# centerbody_logic.net
KiCad netlist of a schematic drawn in EAGLE
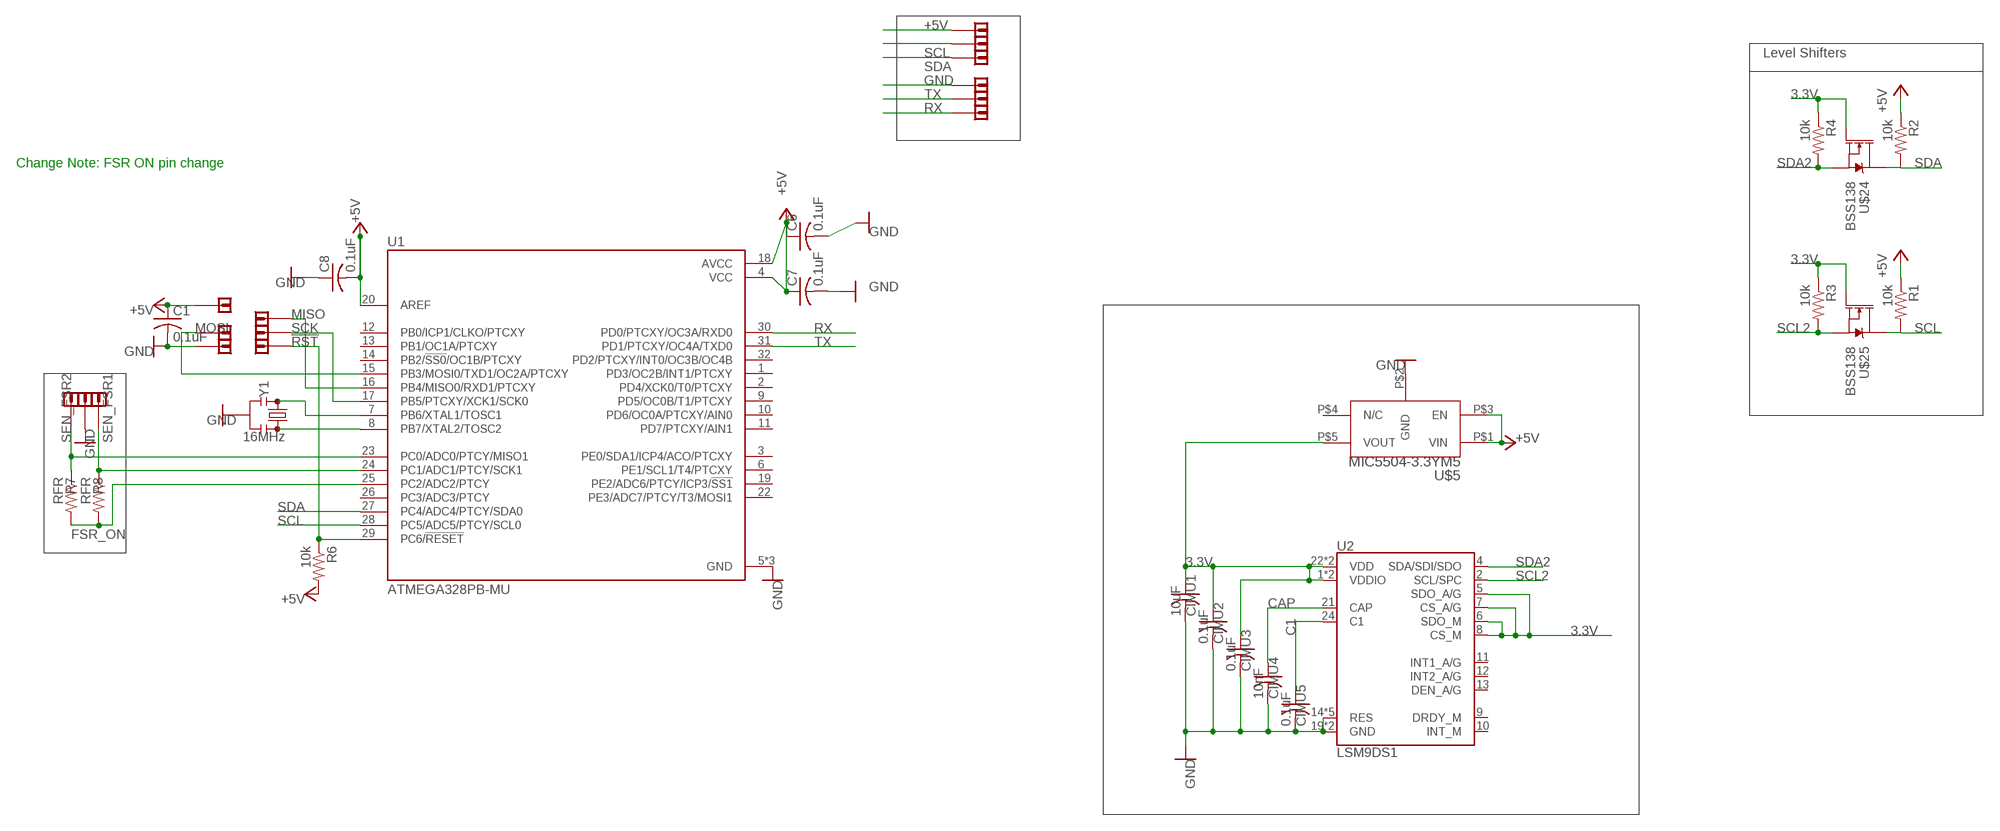
[diagram p0: schematic, sheet 1]

(export (version "E")
  (design (tool "Eeschema 10.0.6"))
  (components
    (comp (ref "C1")
      (value "0.1uF")
      (footprint "eagle-import:C0402")
      (fields (field (name "PARTNO") "885012105010"))
      (libsource (lib "eagle-import") (part "C-USC0402"))
    )
    (comp (ref "C6")
      (value "0.1uF")
      (footprint "eagle-import:C0402")
      (fields (field (name "PARTNO") "885012105010"))
      (libsource (lib "eagle-import") (part "C-USC0402"))
    )
    (comp (ref "C7")
      (value "0.1uF")
      (footprint "eagle-import:C0402")
      (fields (field (name "PARTNO") "885012105010"))
      (libsource (lib "eagle-import") (part "C-USC0402"))
    )
    (comp (ref "C8")
      (value "0.1uF")
      (footprint "eagle-import:C0402")
      (fields (field (name "PARTNO") "885012105010"))
      (libsource (lib "eagle-import") (part "C-USC0402"))
    )
    (comp (ref "CIMU1")
      (value "10uF")
      (footprint "eagle-import:C0402")
      (fields (field (name "PARTNO") "GRM155R60G106ME44D"))
      (libsource (lib "eagle-import") (part "C-USC0402"))
    )
    (comp (ref "CIMU2")
      (value "0.1uF")
      (footprint "eagle-import:C0402")
      (fields (field (name "PARTNO") "885012105010"))
      (libsource (lib "eagle-import") (part "C-USC0402"))
    )
    (comp (ref "CIMU3")
      (value "0.1uF")
      (footprint "eagle-import:C0402")
      (fields (field (name "PARTNO") "885012105010"))
      (libsource (lib "eagle-import") (part "C-USC0402"))
    )
    (comp (ref "CIMU4")
      (value "10nF")
      (footprint "eagle-import:C0402")
      (fields (field (name "PARTNO") "CL05B103KB5NNNC"))
      (libsource (lib "eagle-import") (part "C-USC0402"))
    )
    (comp (ref "CIMU5")
      (value "0.1uF")
      (footprint "eagle-import:C0402")
      (fields (field (name "PARTNO") "885012105010"))
      (libsource (lib "eagle-import") (part "C-USC0402"))
    )
    (comp (ref "R1")
      (value "10k")
      (footprint "eagle-import:R0402")
      (fields (field (name "PARTNO") "RR0510P-103-D"))
      (libsource (lib "eagle-import") (part "R-US_R0402"))
    )
    (comp (ref "R2")
      (value "10k")
      (footprint "eagle-import:R0402")
      (fields (field (name "PARTNO") "RR0510P-103-D"))
      (libsource (lib "eagle-import") (part "R-US_R0402"))
    )
    (comp (ref "R3")
      (value "10k")
      (footprint "eagle-import:R0402")
      (fields (field (name "PARTNO") "RR0510P-103-D"))
      (libsource (lib "eagle-import") (part "R-US_R0402"))
    )
    (comp (ref "R4")
      (value "10k")
      (footprint "eagle-import:R0402")
      (fields (field (name "PARTNO") "RR0510P-103-D"))
      (libsource (lib "eagle-import") (part "R-US_R0402"))
    )
    (comp (ref "R6")
      (value "10k")
      (footprint "eagle-import:R0402")
      (fields (field (name "PARTNO") "RR0510P-103-D"))
      (libsource (lib "eagle-import") (part "R-US_R0402"))
    )
    (comp (ref "R7")
      (value "RFR")
      (footprint "eagle-import:R0402")
      (fields (field (name "PARTNO") "CRGCQ0402F5K6"))
      (libsource (lib "eagle-import") (part "R-US_R0402"))
    )
    (comp (ref "R8")
      (value "RFR")
      (footprint "eagle-import:R0402")
      (fields (field (name "PARTNO") "CRGCQ0402F5K6"))
      (libsource (lib "eagle-import") (part "R-US_R0402"))
    )
    (comp (ref "U$1")
      (value "SIMPLE_VIA_CONNECTION")
      (footprint "eagle-import:SIMPLEVIA")
      (libsource (lib "eagle-import") (part "SIMPLE_VIA_CONNECTION"))
    )
    (comp (ref "U$3")
      (value "SIMPLE_VIA_CONNECTION")
      (footprint "eagle-import:SIMPLEVIA")
      (libsource (lib "eagle-import") (part "SIMPLE_VIA_CONNECTION"))
    )
    (comp (ref "U$4")
      (value "SIMPLE_VIA_CONNECTION")
      (footprint "eagle-import:SIMPLEVIA")
      (libsource (lib "eagle-import") (part "SIMPLE_VIA_CONNECTION"))
    )
    (comp (ref "U$5")
      (value "MIC5504-3.3YM5")
      (footprint "eagle-import:SOT23")
      (fields (field (name "PARTNO") "MIC5504-3.3YM5-TR"))
      (libsource (lib "eagle-import") (part "MIC5504-3.3YM5"))
    )
    (comp (ref "U$6")
      (value "SIMPLE_VIA_CONNECTION")
      (footprint "eagle-import:SIMPLEVIA")
      (libsource (lib "eagle-import") (part "SIMPLE_VIA_CONNECTION"))
    )
    (comp (ref "U$7")
      (value "SIMPLE_VIA_CONNECTION")
      (footprint "eagle-import:SIMPLEVIA")
      (libsource (lib "eagle-import") (part "SIMPLE_VIA_CONNECTION"))
    )
    (comp (ref "U$8")
      (value "SIMPLE_VIA_CONNECTION")
      (footprint "eagle-import:SIMPLEVIA")
      (libsource (lib "eagle-import") (part "SIMPLE_VIA_CONNECTION"))
    )
    (comp (ref "U$9")
      (value "SIMPLE_VIA_CONNECTION")
      (footprint "eagle-import:SIMPLEVIA")
      (libsource (lib "eagle-import") (part "SIMPLE_VIA_CONNECTION"))
    )
    (comp (ref "U$10")
      (value "SIMPLE_VIA_CONNECTION")
      (footprint "eagle-import:SIMPLEVIA")
      (libsource (lib "eagle-import") (part "SIMPLE_VIA_CONNECTION"))
    )
    (comp (ref "U$11")
      (value "SIMPLE_VIA_CONNECTION")
      (footprint "eagle-import:SIMPLEVIA")
      (libsource (lib "eagle-import") (part "SIMPLE_VIA_CONNECTION"))
    )
    (comp (ref "U$12")
      (value "SIMPLE_VIA_CONNECTION")
      (footprint "eagle-import:SIMPLEVIA")
      (libsource (lib "eagle-import") (part "SIMPLE_VIA_CONNECTION"))
    )
    (comp (ref "U$13")
      (value "SIMPLE_VIA_CONNECTION")
      (footprint "eagle-import:SIMPLEVIA")
      (libsource (lib "eagle-import") (part "SIMPLE_VIA_CONNECTION"))
    )
    (comp (ref "U$14")
      (value "SIMPLE_VIA_CONNECTION")
      (footprint "eagle-import:SIMPLEVIA")
      (libsource (lib "eagle-import") (part "SIMPLE_VIA_CONNECTION"))
    )
    (comp (ref "U$15")
      (value "SIMPLE_VIA_CONNECTION")
      (footprint "eagle-import:SIMPLEVIA")
      (libsource (lib "eagle-import") (part "SIMPLE_VIA_CONNECTION"))
    )
    (comp (ref "U$24")
      (value "BSS138")
      (footprint "eagle-import:SOT-23")
      (libsource (lib "eagle-import") (part "BSS138"))
    )
    (comp (ref "U$25")
      (value "BSS138")
      (footprint "eagle-import:SOT-23")
      (libsource (lib "eagle-import") (part "BSS138"))
    )
    (comp (ref "U$26")
      (value "SIMPLE_VIA_CONNECTION")
      (footprint "eagle-import:SIMPLEVIA")
      (libsource (lib "eagle-import") (part "SIMPLE_VIA_CONNECTION"))
    )
    (comp (ref "U$27")
      (value "SIMPLE_VIA_CONNECTION")
      (footprint "eagle-import:SIMPLEVIA")
      (libsource (lib "eagle-import") (part "SIMPLE_VIA_CONNECTION"))
    )
    (comp (ref "U1")
      (value "ATMEGA328PB-MU")
      (footprint "eagle-import:QFN50P500X500X90-33N")
      (fields
        (field (name "DIGI-KEY_PART_NUMBER") "ATMEGA328PB-MU-ND")
        (field (name "MF") "Microchip")
        (field (name "PARTNO") "ATMEGA328PB-MUR")
      )
      (libsource (lib "eagle-import") (part "ATMEGA328PB-MU"))
    )
    (comp (ref "U2")
      (value "LSM9DS1")
      (footprint "eagle-import:LGA24-8X4")
      (fields (field (name "PARTNO") "LSM9DS1TR"))
      (libsource (lib "eagle-import") (part "LSM9DS1"))
    )
    (comp (ref "Y1")
      (value "16MHz")
      (footprint "eagle-import:RESONATOR-SMD-3.2X1.3")
      (fields (field (name "PARTNO") "CSTNE16M0V530000R0"))
      (libsource (lib "eagle-import") (part "RESONATOR-16MHZSMD_3.2X1.3"))
    )
  )
  (nets
    (net (code "1") (name "+5V") (class "Default")
      (node (ref "C1") (pin "1") (pinfunction "1_1") (pintype "passive"))
      (node (ref "C6") (pin "1") (pinfunction "1_1") (pintype "passive"))
      (node (ref "C7") (pin "1") (pinfunction "1_1") (pintype "passive"))
      (node (ref "C8") (pin "2") (pinfunction "2_2") (pintype "passive"))
      (node (ref "R1") (pin "1") (pinfunction "1_1") (pintype "passive"))
      (node (ref "R2") (pin "1") (pinfunction "1_1") (pintype "passive"))
      (node (ref "R6") (pin "2") (pinfunction "2_2") (pintype "passive"))
      (node (ref "U$10") (pin "P$1") (pinfunction "1_P$1") (pintype "passive"))
      (node (ref "U$5") (pin "P$1") (pinfunction "VIN_P$1") (pintype "bidirectional"))
      (node (ref "U$5") (pin "P$3") (pinfunction "EN_P$3") (pintype "bidirectional"))
      (node (ref "U$7") (pin "P$1") (pinfunction "1_P$1") (pintype "passive"))
      (node (ref "U1") (pin "18") (pinfunction "AVCC_18") (pintype "power_in"))
      (node (ref "U1") (pin "20") (pinfunction "AREF_20") (pintype "input"))
      (node (ref "U1") (pin "4") (pinfunction "VCC_4") (pintype "power_in"))
    )
    (net (code "2") (name "/3.3V") (class "Default")
      (node (ref "CIMU1") (pin "1") (pinfunction "1_1") (pintype "passive"))
      (node (ref "CIMU2") (pin "1") (pinfunction "1_1") (pintype "passive"))
      (node (ref "CIMU3") (pin "1") (pinfunction "1_1") (pintype "passive"))
      (node (ref "R3") (pin "1") (pinfunction "1_1") (pintype "passive"))
      (node (ref "R4") (pin "1") (pinfunction "1_1") (pintype "passive"))
      (node (ref "U$24") (pin "P$1") (pinfunction "G_P$1") (pintype "bidirectional"))
      (node (ref "U$25") (pin "P$1") (pinfunction "G_P$1") (pintype "bidirectional"))
      (node (ref "U$5") (pin "P$5") (pinfunction "VOUT_P$5") (pintype "bidirectional"))
      (node (ref "U2") (pin "1") (pinfunction "VDDIO_1") (pintype "bidirectional"))
      (node (ref "U2") (pin "22") (pinfunction "VDD_22") (pintype "bidirectional"))
      (node (ref "U2") (pin "23") (pinfunction "VDD_23") (pintype "bidirectional"))
      (node (ref "U2") (pin "3") (pinfunction "VDDIO_3") (pintype "bidirectional"))
      (node (ref "U2") (pin "5") (pinfunction "SDO_A/G_5") (pintype "bidirectional"))
      (node (ref "U2") (pin "6") (pinfunction "SDO_M_6") (pintype "bidirectional"))
      (node (ref "U2") (pin "7") (pinfunction "CS_A/G_7") (pintype "bidirectional"))
      (node (ref "U2") (pin "8") (pinfunction "CS_M_8") (pintype "bidirectional"))
    )
    (net (code "3") (name "/C1") (class "Default")
      (node (ref "CIMU5") (pin "1") (pinfunction "1_1") (pintype "passive"))
      (node (ref "U2") (pin "24") (pinfunction "C1_24") (pintype "bidirectional"))
    )
    (net (code "4") (name "/CAP") (class "Default")
      (node (ref "CIMU4") (pin "1") (pinfunction "1_1") (pintype "passive"))
      (node (ref "U2") (pin "21") (pinfunction "CAP_21") (pintype "bidirectional"))
    )
    (net (code "5") (name "/FSR_ON") (class "Default")
      (node (ref "R7") (pin "2") (pinfunction "2_2") (pintype "passive"))
      (node (ref "R8") (pin "2") (pinfunction "2_2") (pintype "passive"))
      (node (ref "U1") (pin "25") (pinfunction "PC2/ADC2/PTCY_25") (pintype "bidirectional"))
    )
    (net (code "6") (name "/MISO") (class "Default")
      (node (ref "U$15") (pin "P$1") (pinfunction "1_P$1") (pintype "passive"))
      (node (ref "U1") (pin "16") (pinfunction "PB4/MISO0/RXD1/PTCXY_16") (pintype "bidirectional"))
    )
    (net (code "7") (name "/MOSI") (class "Default")
      (node (ref "U$11") (pin "P$1") (pinfunction "1_P$1") (pintype "passive"))
      (node (ref "U1") (pin "15") (pinfunction "PB3/MOSI0/TXD1/OC2A/PTCXY_15") (pintype "bidirectional"))
    )
    (net (code "8") (name "/RX") (class "Default")
      (node (ref "U$27") (pin "P$1") (pinfunction "1_P$1") (pintype "passive"))
      (node (ref "U1") (pin "30") (pinfunction "PD0/PTCXY/OC3A/RXD0_30") (pintype "bidirectional"))
    )
    (net (code "9") (name "/SCK") (class "Default")
      (node (ref "U$14") (pin "P$1") (pinfunction "1_P$1") (pintype "passive"))
      (node (ref "U1") (pin "17") (pinfunction "PB5/PTCXY/XCK1/SCK0_17") (pintype "bidirectional"))
    )
    (net (code "10") (name "/SCL") (class "Default")
      (node (ref "R1") (pin "2") (pinfunction "2_2") (pintype "passive"))
      (node (ref "U$25") (pin "P$3") (pinfunction "D_P$3") (pintype "bidirectional"))
      (node (ref "U$9") (pin "P$1") (pinfunction "1_P$1") (pintype "passive"))
      (node (ref "U1") (pin "28") (pinfunction "PC5/ADC5/PTCY/SCL0_28") (pintype "bidirectional"))
    )
    (net (code "11") (name "/SCL2") (class "Default")
      (node (ref "R3") (pin "2") (pinfunction "2_2") (pintype "passive"))
      (node (ref "U$25") (pin "P$2") (pinfunction "S_P$2") (pintype "bidirectional"))
      (node (ref "U2") (pin "2") (pinfunction "SCL/SPC_2") (pintype "bidirectional"))
    )
    (net (code "12") (name "/SDA") (class "Default")
      (node (ref "R2") (pin "2") (pinfunction "2_2") (pintype "passive"))
      (node (ref "U$24") (pin "P$3") (pinfunction "D_P$3") (pintype "bidirectional"))
      (node (ref "U$4") (pin "P$1") (pinfunction "1_P$1") (pintype "passive"))
      (node (ref "U1") (pin "27") (pinfunction "PC4/ADC4/PTCY/SDA0_27") (pintype "bidirectional"))
    )
    (net (code "13") (name "/SDA2") (class "Default")
      (node (ref "R4") (pin "2") (pinfunction "2_2") (pintype "passive"))
      (node (ref "U$24") (pin "P$2") (pinfunction "S_P$2") (pintype "bidirectional"))
      (node (ref "U2") (pin "4") (pinfunction "SDA/SDI/SDO_4") (pintype "bidirectional"))
    )
    (net (code "14") (name "/SEN_FSR1") (class "Default")
      (node (ref "R8") (pin "1") (pinfunction "1_1") (pintype "passive"))
      (node (ref "U$8") (pin "P$1") (pinfunction "1_P$1") (pintype "passive"))
      (node (ref "U1") (pin "24") (pinfunction "PC1/ADC1/PTCY/SCK1_24") (pintype "bidirectional"))
    )
    (net (code "15") (name "/SEN_FSR2") (class "Default")
      (node (ref "R7") (pin "1") (pinfunction "1_1") (pintype "passive"))
      (node (ref "U$1") (pin "P$1") (pinfunction "1_P$1") (pintype "passive"))
      (node (ref "U1") (pin "23") (pinfunction "PC0/ADC0/PTCY/MISO1_23") (pintype "bidirectional"))
    )
    (net (code "16") (name "/TX") (class "Default")
      (node (ref "U$26") (pin "P$1") (pinfunction "1_P$1") (pintype "passive"))
      (node (ref "U1") (pin "31") (pinfunction "PD1/PTCXY/OC4A/TXD0_31") (pintype "bidirectional"))
    )
    (net (code "17") (name "/~{RST}") (class "Default")
      (node (ref "R6") (pin "1") (pinfunction "1_1") (pintype "passive"))
      (node (ref "U$13") (pin "P$1") (pinfunction "1_P$1") (pintype "passive"))
      (node (ref "U1") (pin "29") (pinfunction "PC6/~{RESET}_29") (pintype "bidirectional"))
    )
    (net (code "18") (name "GND") (class "Default")
      (node (ref "C1") (pin "2") (pinfunction "2_2") (pintype "passive"))
      (node (ref "C6") (pin "2") (pinfunction "2_2") (pintype "passive"))
      (node (ref "C7") (pin "2") (pinfunction "2_2") (pintype "passive"))
      (node (ref "C8") (pin "1") (pinfunction "1_1") (pintype "passive"))
      (node (ref "CIMU1") (pin "2") (pinfunction "2_2") (pintype "passive"))
      (node (ref "CIMU2") (pin "2") (pinfunction "2_2") (pintype "passive"))
      (node (ref "CIMU3") (pin "2") (pinfunction "2_2") (pintype "passive"))
      (node (ref "CIMU4") (pin "2") (pinfunction "2_2") (pintype "passive"))
      (node (ref "CIMU5") (pin "2") (pinfunction "2_2") (pintype "passive"))
      (node (ref "U$12") (pin "P$1") (pinfunction "1_P$1") (pintype "passive"))
      (node (ref "U$3") (pin "P$1") (pinfunction "1_P$1") (pintype "passive"))
      (node (ref "U$5") (pin "P$2") (pinfunction "GND_P$2") (pintype "bidirectional"))
      (node (ref "U$6") (pin "P$1") (pinfunction "1_P$1") (pintype "passive"))
      (node (ref "U1") (pin "21") (pinfunction "GND_21") (pintype "power_in"))
      (node (ref "U1") (pin "33") (pinfunction "GND_33") (pintype "power_in"))
      (node (ref "U1") (pin "5") (pinfunction "GND_5") (pintype "power_in"))
      (node (ref "U2") (pin "14") (pinfunction "RES_14") (pintype "bidirectional"))
      (node (ref "U2") (pin "15") (pinfunction "RES_15") (pintype "bidirectional"))
      (node (ref "U2") (pin "16") (pinfunction "RES_16") (pintype "bidirectional"))
      (node (ref "U2") (pin "17") (pinfunction "RES_17") (pintype "bidirectional"))
      (node (ref "U2") (pin "18") (pinfunction "RES_18") (pintype "bidirectional"))
      (node (ref "U2") (pin "19") (pinfunction "GND_19") (pintype "bidirectional"))
      (node (ref "U2") (pin "20") (pinfunction "GND_20") (pintype "bidirectional"))
      (node (ref "Y1") (pin "2") (pinfunction "2_2") (pintype "passive"))
    )
    (net (code "19") (name "Net-(U1-PB6{slash}XTAL1{slash}TOSC1)") (class "Default")
      (node (ref "U1") (pin "7") (pinfunction "PB6/XTAL1/TOSC1_7") (pintype "bidirectional"))
      (node (ref "Y1") (pin "1") (pinfunction "1_1") (pintype "passive"))
    )
    (net (code "20") (name "Net-(U1-PB7{slash}XTAL2{slash}TOSC2)") (class "Default")
      (node (ref "U1") (pin "8") (pinfunction "PB7/XTAL2/TOSC2_8") (pintype "bidirectional"))
      (node (ref "Y1") (pin "3") (pinfunction "3_3") (pintype "passive"))
    )
    (net (code "21") (name "unconnected-(U$5-N{slash}C-PadP$4)") (class "Default")
      (node (ref "U$5") (pin "P$4") (pinfunction "N/C_P$4") (pintype "bidirectional"))
    )
    (net (code "22") (name "unconnected-(U1-PB0{slash}ICP1{slash}CLKO{slash}PTCXY-Pad12)") (class "Default")
      (node (ref "U1") (pin "12") (pinfunction "PB0/ICP1/CLKO/PTCXY_12") (pintype "bidirectional"))
    )
    (net (code "23") (name "unconnected-(U1-PB1{slash}OC1A{slash}PTCXY-Pad13)") (class "Default")
      (node (ref "U1") (pin "13") (pinfunction "PB1/OC1A/PTCXY_13") (pintype "bidirectional"))
    )
    (net (code "24") (name "unconnected-(U1-PB2{slash}~{SS0}{slash}OC1B{slash}PTCXY-Pad14)") (class "Default")
      (node (ref "U1") (pin "14") (pinfunction "PB2/~{SS0}/OC1B/PTCXY_14") (pintype "bidirectional"))
    )
    (net (code "25") (name "unconnected-(U1-PC3{slash}ADC3{slash}PTCY-Pad26)") (class "Default")
      (node (ref "U1") (pin "26") (pinfunction "PC3/ADC3/PTCY_26") (pintype "bidirectional"))
    )
    (net (code "26") (name "unconnected-(U1-PD2{slash}PTCXY{slash}INT0{slash}OC3B{slash}OC4B-Pad32)") (class "Default")
      (node (ref "U1") (pin "32") (pinfunction "PD2/PTCXY/INT0/OC3B/OC4B_32") (pintype "bidirectional"))
    )
    (net (code "27") (name "unconnected-(U1-PD3{slash}OC2B{slash}INT1{slash}PTCXY-Pad1)") (class "Default")
      (node (ref "U1") (pin "1") (pinfunction "PD3/OC2B/INT1/PTCXY_1") (pintype "bidirectional"))
    )
    (net (code "28") (name "unconnected-(U1-PD4{slash}XCK0{slash}T0{slash}PTCXY-Pad2)") (class "Default")
      (node (ref "U1") (pin "2") (pinfunction "PD4/XCK0/T0/PTCXY_2") (pintype "bidirectional"))
    )
    (net (code "29") (name "unconnected-(U1-PD5{slash}OC0B{slash}T1{slash}PTCXY-Pad9)") (class "Default")
      (node (ref "U1") (pin "9") (pinfunction "PD5/OC0B/T1/PTCXY_9") (pintype "bidirectional"))
    )
    (net (code "30") (name "unconnected-(U1-PD6{slash}OC0A{slash}PTCXY{slash}AIN0-Pad10)") (class "Default")
      (node (ref "U1") (pin "10") (pinfunction "PD6/OC0A/PTCXY/AIN0_10") (pintype "bidirectional"))
    )
    (net (code "31") (name "unconnected-(U1-PD7{slash}PTCXY{slash}AIN1-Pad11)") (class "Default")
      (node (ref "U1") (pin "11") (pinfunction "PD7/PTCXY/AIN1_11") (pintype "bidirectional"))
    )
    (net (code "32") (name "unconnected-(U1-PE0{slash}SDA1{slash}ICP4{slash}ACO{slash}PTCXY-Pad3)") (class "Default")
      (node (ref "U1") (pin "3") (pinfunction "PE0/SDA1/ICP4/ACO/PTCXY_3") (pintype "bidirectional"))
    )
    (net (code "33") (name "unconnected-(U1-PE1{slash}SCL1{slash}T4{slash}PTCXY-Pad6)") (class "Default")
      (node (ref "U1") (pin "6") (pinfunction "PE1/SCL1/T4/PTCXY_6") (pintype "bidirectional"))
    )
    (net (code "34") (name "unconnected-(U1-PE2{slash}ADC6{slash}PTCY{slash}ICP3{slash}~{SS1}-Pad19)") (class "Default")
      (node (ref "U1") (pin "19") (pinfunction "PE2/ADC6/PTCY/ICP3/~{SS1}_19") (pintype "bidirectional"))
    )
    (net (code "35") (name "unconnected-(U1-PE3{slash}ADC7{slash}PTCY{slash}T3{slash}MOSI1-Pad22)") (class "Default")
      (node (ref "U1") (pin "22") (pinfunction "PE3/ADC7/PTCY/T3/MOSI1_22") (pintype "bidirectional"))
    )
    (net (code "36") (name "unconnected-(U2-DEN_A{slash}G-Pad13)") (class "Default")
      (node (ref "U2") (pin "13") (pinfunction "DEN_A/G_13") (pintype "bidirectional"))
    )
    (net (code "37") (name "unconnected-(U2-DRDY_M-Pad9)") (class "Default")
      (node (ref "U2") (pin "9") (pinfunction "DRDY_M_9") (pintype "bidirectional"))
    )
    (net (code "38") (name "unconnected-(U2-INT1_A{slash}G-Pad11)") (class "Default")
      (node (ref "U2") (pin "11") (pinfunction "INT1_A/G_11") (pintype "bidirectional"))
    )
    (net (code "39") (name "unconnected-(U2-INT2_A{slash}G-Pad12)") (class "Default")
      (node (ref "U2") (pin "12") (pinfunction "INT2_A/G_12") (pintype "bidirectional"))
    )
    (net (code "40") (name "unconnected-(U2-INT_M-Pad10)") (class "Default")
      (node (ref "U2") (pin "10") (pinfunction "INT_M_10") (pintype "bidirectional"))
    )
  )
)
